# DM2097_IMX378.net
KiCad netlist of a schematic drawn in Altium Designer
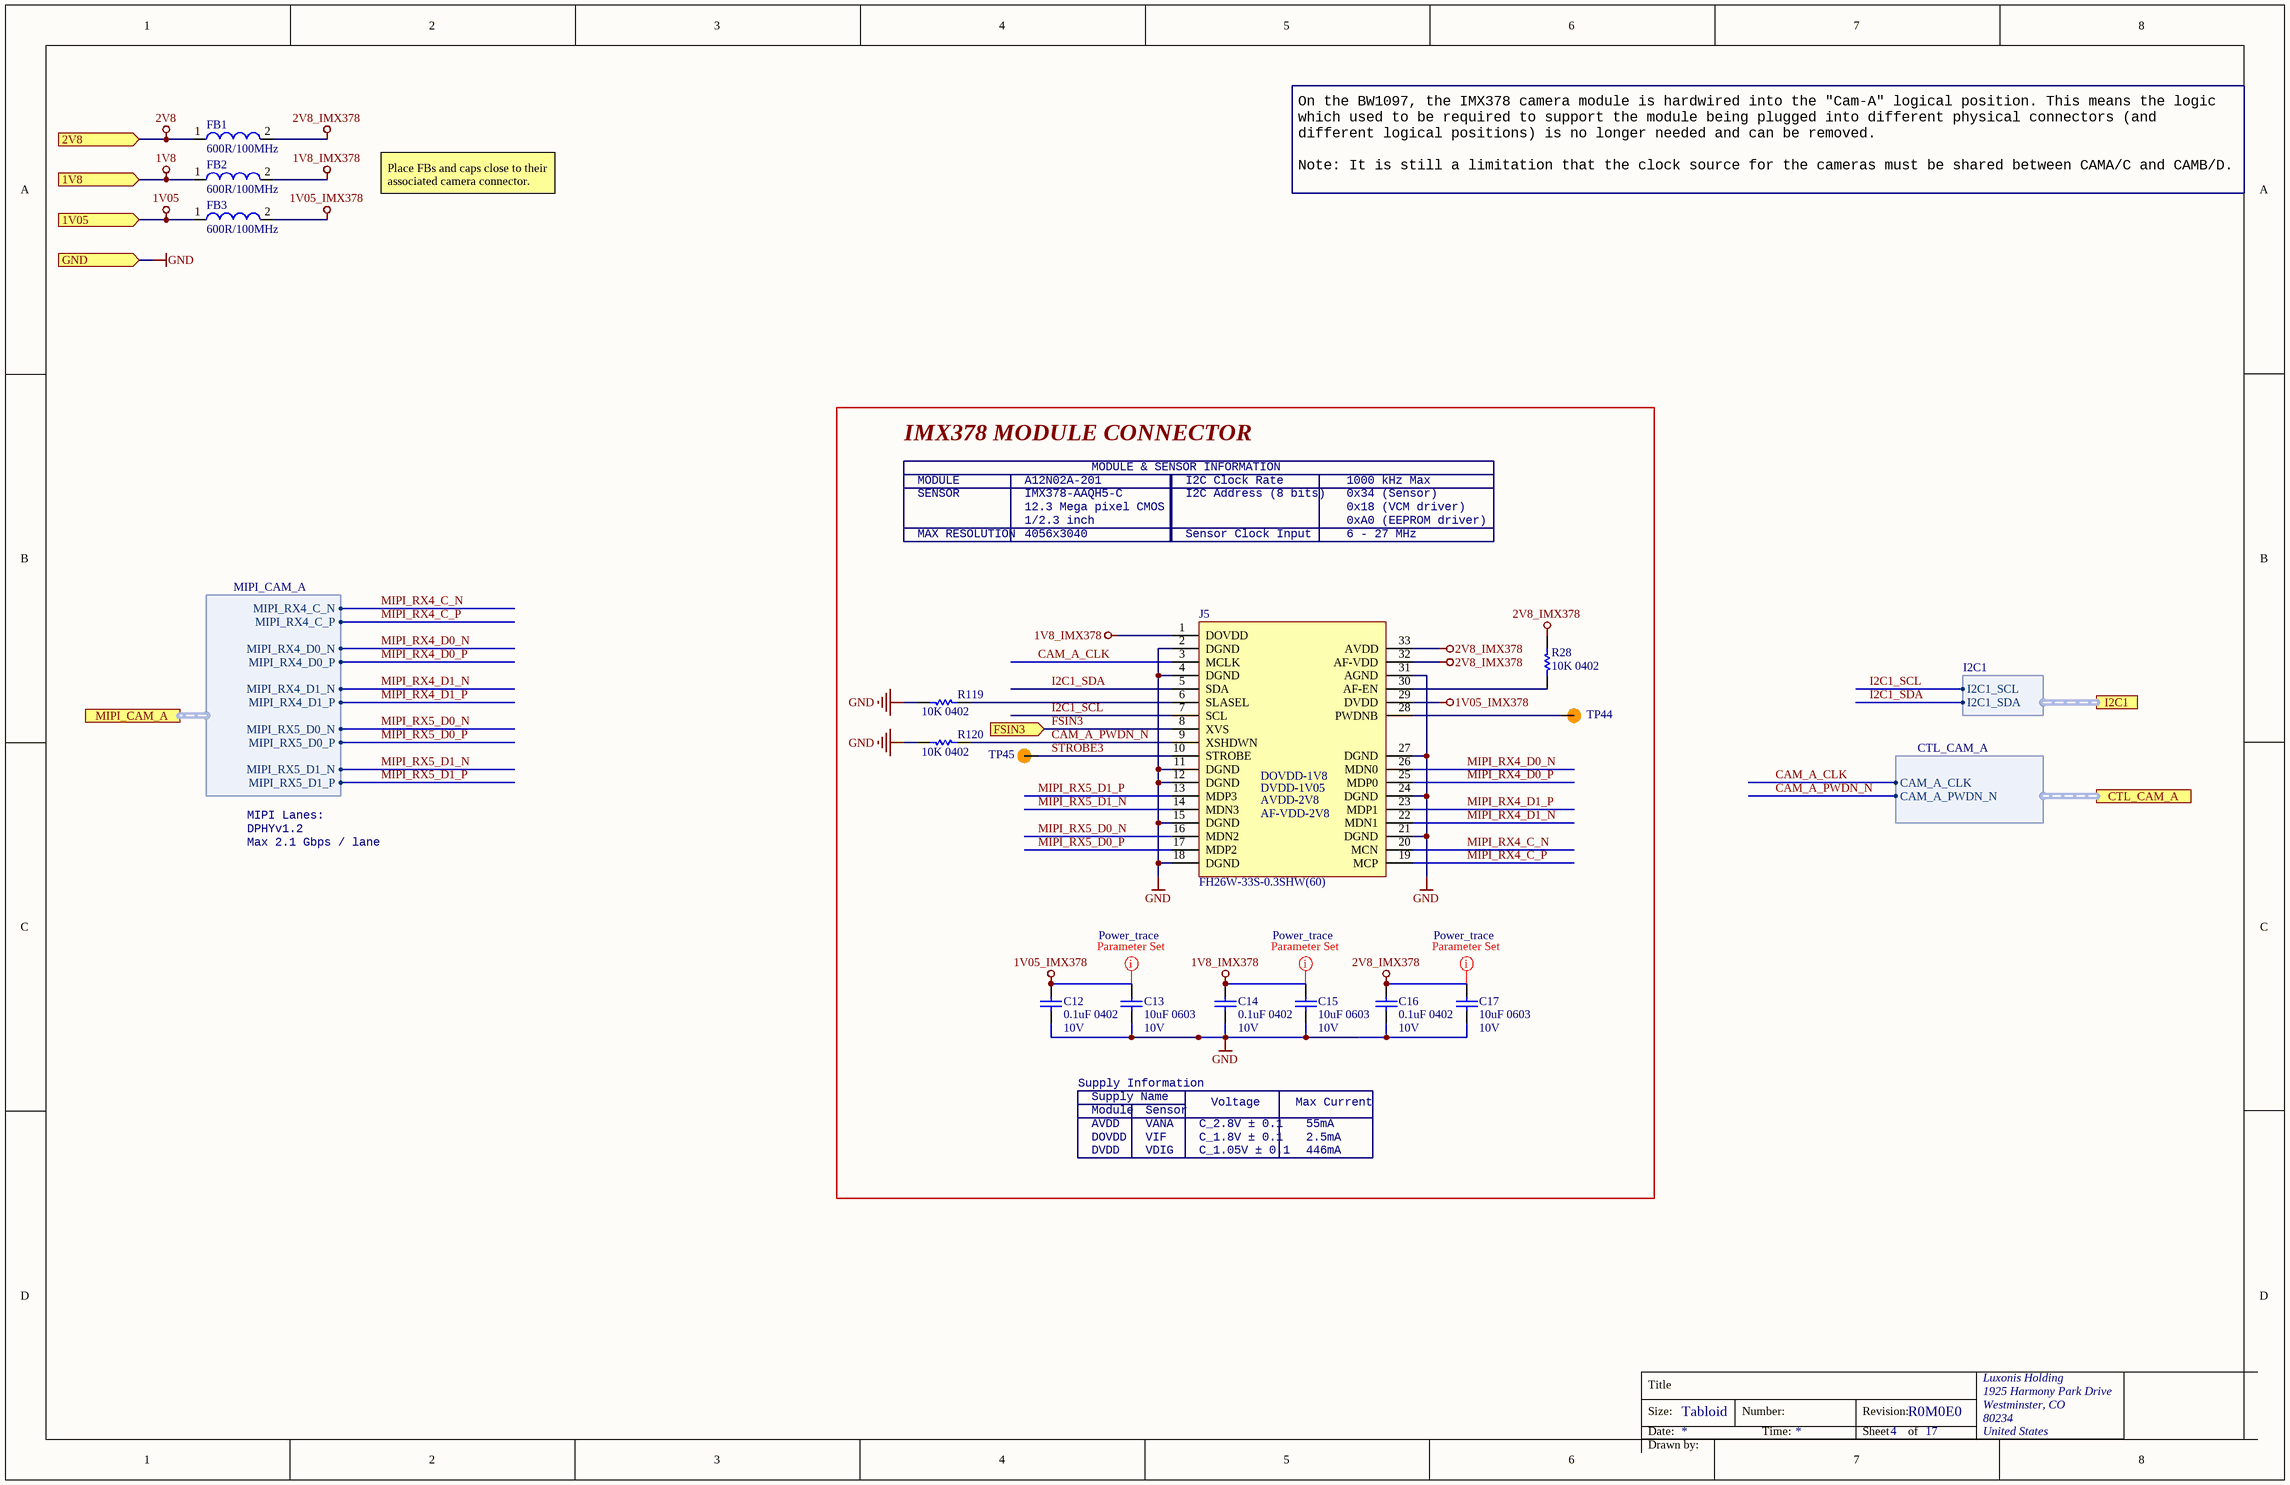
[diagram p0: DM2097_IMX378.SchDoc]

(export (version "E")
  (design (tool "Eeschema 10.0.6"))
  (components
    (comp (ref "C12")
      (value "0.1uF 0402")
      (footprint "CAP_Altium_Vault_Generic:CAPC0402(1005)70_L")
      (description "CAP CER 0.1UF 10V X7R 0402 5%")
      (fields (field (name "TOLERANCE") "5%") (field (name "VOLTAGE RATING") "10V"))
      (libsource (lib "LuxonisMaster") (part "GRM155R71A104JA01D"))
    )
    (comp (ref "C13")
      (value "10uF 0603")
      (footprint "CAP_Altium_Vault_Generic:CAPC0603(1608)100_L")
      (description "CAP CER 10UF 10V X5R 0603 20%")
      (fields (field (name "TOLERANCE") "20%") (field (name "VOLTAGE RATING") "10V"))
      (libsource (lib "LuxonisMaster") (part "GRM188R61A106ME69D"))
    )
    (comp (ref "C14")
      (value "0.1uF 0402")
      (footprint "CAP_Altium_Vault_Generic:CAPC0402(1005)70_L")
      (description "CAP CER 0.1UF 10V X7R 0402 5%")
      (fields (field (name "TOLERANCE") "5%") (field (name "VOLTAGE RATING") "10V"))
      (libsource (lib "LuxonisMaster") (part "GRM155R71A104JA01D"))
    )
    (comp (ref "C15")
      (value "10uF 0603")
      (footprint "CAP_Altium_Vault_Generic:CAPC0603(1608)100_L")
      (description "CAP CER 10UF 10V X5R 0603 20%")
      (fields (field (name "TOLERANCE") "20%") (field (name "VOLTAGE RATING") "10V"))
      (libsource (lib "LuxonisMaster") (part "GRM188R61A106ME69D"))
    )
    (comp (ref "C16")
      (value "0.1uF 0402")
      (footprint "CAP_Altium_Vault_Generic:CAPC0402(1005)70_L")
      (description "CAP CER 0.1UF 10V X7R 0402 5%")
      (fields (field (name "TOLERANCE") "5%") (field (name "VOLTAGE RATING") "10V"))
      (libsource (lib "LuxonisMaster") (part "GRM155R71A104JA01D"))
    )
    (comp (ref "C17")
      (value "10uF 0603")
      (footprint "CAP_Altium_Vault_Generic:CAPC0603(1608)100_L")
      (description "CAP CER 10UF 10V X5R 0603 20%")
      (fields (field (name "TOLERANCE") "20%") (field (name "VOLTAGE RATING") "10V"))
      (libsource (lib "LuxonisMaster") (part "GRM188R61A106ME69D"))
    )
    (comp (ref "FB1")
      (value "600R/100MHz")
      (footprint "LuxonisMaster:2508056017Y2")
      (description "FERRITE BEAD, 0.1OHM, 2A, 0805, 600R/100MHz")
      (fields (field (name "TOLERANCE") "25%"))
      (libsource (lib "LuxonisMaster") (part "2508056017Y2"))
    )
    (comp (ref "FB2")
      (value "600R/100MHz")
      (footprint "LuxonisMaster:2508056017Y2")
      (description "FERRITE BEAD, 0.1OHM, 2A, 0805, 600R/100MHz")
      (fields (field (name "TOLERANCE") "25%"))
      (libsource (lib "LuxonisMaster") (part "2508056017Y2"))
    )
    (comp (ref "FB3")
      (value "600R/100MHz")
      (footprint "LuxonisMaster:2508056017Y2")
      (description "FERRITE BEAD, 0.1OHM, 2A, 0805, 600R/100MHz")
      (fields (field (name "TOLERANCE") "25%"))
      (libsource (lib "LuxonisMaster") (part "2508056017Y2"))
    )
    (comp (ref "J5")
      (value "FH26W-33S-0.3SHW(60)")
      (footprint "AC-PY004-IMX378")
      (description "FFC/FPC Connector, 33 Contact(s), 1 Row(s), Female, Right Angle, Surface Mount Terminal")
      (libsource (lib "DM9098") (part "AC_PY004-IMX378_CON"))
    )
    (comp (ref "R28")
      (value "10K 0402")
      (footprint "RES_Altium_Vault_Generic:RESC0402(1005)_L")
      (fields (field (name "TOLERANCE") "1%"))
      (libsource (lib "LuxonisMaster") (part "RC0402FR-1310KL"))
    )
    (comp (ref "R119")
      (value "10K 0402")
      (footprint "RES_Altium_Vault_Generic:RESC0402(1005)_L")
      (fields (field (name "TOLERANCE") "1%"))
      (libsource (lib "LuxonisMaster") (part "RC0402FR-1310KL"))
    )
    (comp (ref "R120")
      (value "10K 0402")
      (footprint "RES_Altium_Vault_Generic:RESC0402(1005)_L")
      (fields (field (name "TOLERANCE") "1%"))
      (libsource (lib "LuxonisMaster") (part "RC0402FR-1310KL"))
    )
    (comp (ref "TP44")
      (value "TP100_200_NS")
      (footprint "LuxonisMaster:TP100_200_NS")
      (libsource (lib "LuxonisMaster") (part "TEST_POINT"))
    )
    (comp (ref "TP45")
      (value "TP100_200_NS")
      (footprint "LuxonisMaster:TP100_200_NS")
      (libsource (lib "LuxonisMaster") (part "TEST_POINT"))
    )
  )
  (nets
    (net (code "4") (name "/CAM_A_CLK") (class "Default")
      (node (ref "J5") (pin "3") (pinfunction "MCLK_3") (pintype "passive"))
    )
    (net (code "5") (name "/CAM_A_PWDN_N") (class "Default")
      (node (ref "J5") (pin "9") (pinfunction "XSHDWN_9") (pintype "passive"))
      (node (ref "R120") (pin "1") (pinfunction "1_1") (pintype "passive"))
    )
    (net (code "6") (name "/FSIN3") (class "Default")
      (node (ref "J5") (pin "8") (pinfunction "XVS_8") (pintype "passive"))
    )
    (net (code "7") (name "/I2C1_SCL") (class "Default")
      (node (ref "J5") (pin "7") (pinfunction "SCL_7") (pintype "passive"))
    )
    (net (code "8") (name "/I2C1_SDA") (class "Default")
      (node (ref "J5") (pin "5") (pinfunction "SDA_5") (pintype "passive"))
    )
    (net (code "9") (name "/MIPI_RX4_C_N") (class "Default")
      (node (ref "J5") (pin "20") (pinfunction "MCN_20") (pintype "passive"))
    )
    (net (code "10") (name "/MIPI_RX4_C_P") (class "Default")
      (node (ref "J5") (pin "19") (pinfunction "MCP_19") (pintype "passive"))
    )
    (net (code "11") (name "/MIPI_RX4_D0_N") (class "Default")
      (node (ref "J5") (pin "26") (pinfunction "MDN0_26") (pintype "passive"))
    )
    (net (code "12") (name "/MIPI_RX4_D0_P") (class "Default")
      (node (ref "J5") (pin "25") (pinfunction "MDP0_25") (pintype "passive"))
    )
    (net (code "13") (name "/MIPI_RX4_D1_N") (class "Default")
      (node (ref "J5") (pin "22") (pinfunction "MDN1_22") (pintype "passive"))
    )
    (net (code "14") (name "/MIPI_RX4_D1_P") (class "Default")
      (node (ref "J5") (pin "23") (pinfunction "MDP1_23") (pintype "passive"))
    )
    (net (code "15") (name "/MIPI_RX5_D0_N") (class "Default")
      (node (ref "J5") (pin "16") (pinfunction "MDN2_16") (pintype "passive"))
    )
    (net (code "16") (name "/MIPI_RX5_D0_P") (class "Default")
      (node (ref "J5") (pin "17") (pinfunction "MDP2_17") (pintype "passive"))
    )
    (net (code "17") (name "/MIPI_RX5_D1_N") (class "Default")
      (node (ref "J5") (pin "14") (pinfunction "MDN3_14") (pintype "passive"))
    )
    (net (code "18") (name "/MIPI_RX5_D1_P") (class "Default")
      (node (ref "J5") (pin "13") (pinfunction "MDP3_13") (pintype "passive"))
    )
    (net (code "19") (name "/STROBE3") (class "Default")
      (node (ref "J5") (pin "10") (pinfunction "STROBE_10") (pintype "passive"))
      (node (ref "TP45") (pin "1") (pintype "passive"))
    )
    (net (code "23") (name "1V05") (class "Default")
      (node (ref "FB3") (pin "1") (pinfunction "1_1") (pintype "passive"))
    )
    (net (code "24") (name "1V05_IMX378") (class "Default")
      (node (ref "C12") (pin "2") (pinfunction "2_2") (pintype "passive"))
      (node (ref "C13") (pin "2") (pinfunction "2_2") (pintype "passive"))
      (node (ref "FB3") (pin "2") (pinfunction "2_2") (pintype "passive"))
      (node (ref "J5") (pin "29") (pinfunction "DVDD_29") (pintype "passive"))
    )
    (net (code "25") (name "1V8") (class "Default")
      (node (ref "FB2") (pin "1") (pinfunction "1_1") (pintype "passive"))
    )
    (net (code "26") (name "1V8_IMX378") (class "Default")
      (node (ref "C14") (pin "2") (pinfunction "2_2") (pintype "passive"))
      (node (ref "C15") (pin "2") (pinfunction "2_2") (pintype "passive"))
      (node (ref "FB2") (pin "2") (pinfunction "2_2") (pintype "passive"))
      (node (ref "J5") (pin "1") (pinfunction "DOVDD_1") (pintype "passive"))
    )
    (net (code "27") (name "2V8") (class "Default")
      (node (ref "FB1") (pin "1") (pinfunction "1_1") (pintype "passive"))
    )
    (net (code "28") (name "2V8_IMX378") (class "Default")
      (node (ref "C16") (pin "2") (pinfunction "2_2") (pintype "passive"))
      (node (ref "C17") (pin "2") (pinfunction "2_2") (pintype "passive"))
      (node (ref "FB1") (pin "2") (pinfunction "2_2") (pintype "passive"))
      (node (ref "J5") (pin "32") (pinfunction "AF-VDD_32") (pintype "passive"))
      (node (ref "J5") (pin "33") (pinfunction "AVDD_33") (pintype "passive"))
      (node (ref "R28") (pin "1") (pinfunction "1_1") (pintype "passive"))
    )
    (net (code "29") (name "GND") (class "Default")
      (node (ref "C12") (pin "1") (pinfunction "1_1") (pintype "passive"))
      (node (ref "C13") (pin "1") (pinfunction "1_1") (pintype "passive"))
      (node (ref "C14") (pin "1") (pinfunction "1_1") (pintype "passive"))
      (node (ref "C15") (pin "1") (pinfunction "1_1") (pintype "passive"))
      (node (ref "C16") (pin "1") (pinfunction "1_1") (pintype "passive"))
      (node (ref "C17") (pin "1") (pinfunction "1_1") (pintype "passive"))
      (node (ref "J5") (pin "11") (pinfunction "DGND_11") (pintype "passive"))
      (node (ref "J5") (pin "12") (pinfunction "DGND_12") (pintype "passive"))
      (node (ref "J5") (pin "15") (pinfunction "DGND_15") (pintype "passive"))
      (node (ref "J5") (pin "18") (pinfunction "DGND_18") (pintype "passive"))
      (node (ref "J5") (pin "2") (pinfunction "DGND_2") (pintype "passive"))
      (node (ref "J5") (pin "21") (pinfunction "DGND_21") (pintype "passive"))
      (node (ref "J5") (pin "24") (pinfunction "DGND_24") (pintype "passive"))
      (node (ref "J5") (pin "27") (pinfunction "DGND_27") (pintype "passive"))
      (node (ref "J5") (pin "31") (pinfunction "AGND_31") (pintype "passive"))
      (node (ref "J5") (pin "4") (pinfunction "DGND_4") (pintype "passive"))
      (node (ref "R119") (pin "2") (pinfunction "2_2") (pintype "passive"))
      (node (ref "R120") (pin "2") (pinfunction "2_2") (pintype "passive"))
    )
    (net (code "30") (name "Net-(J5-AF-EN)") (class "Default")
      (node (ref "J5") (pin "30") (pinfunction "AF-EN_30") (pintype "passive"))
      (node (ref "R28") (pin "2") (pinfunction "2_2") (pintype "passive"))
    )
    (net (code "31") (name "Net-(J5-PWDNB)") (class "Default")
      (node (ref "J5") (pin "28") (pinfunction "PWDNB_28") (pintype "passive"))
      (node (ref "TP44") (pin "1") (pintype "passive"))
    )
    (net (code "32") (name "Net-(J5-SLASEL)") (class "Default")
      (node (ref "J5") (pin "6") (pinfunction "SLASEL_6") (pintype "passive"))
      (node (ref "R119") (pin "1") (pinfunction "1_1") (pintype "passive"))
    )
  )
)
